# SoC_pwr_2.net
KiCad netlist of a schematic drawn in Altium Designer
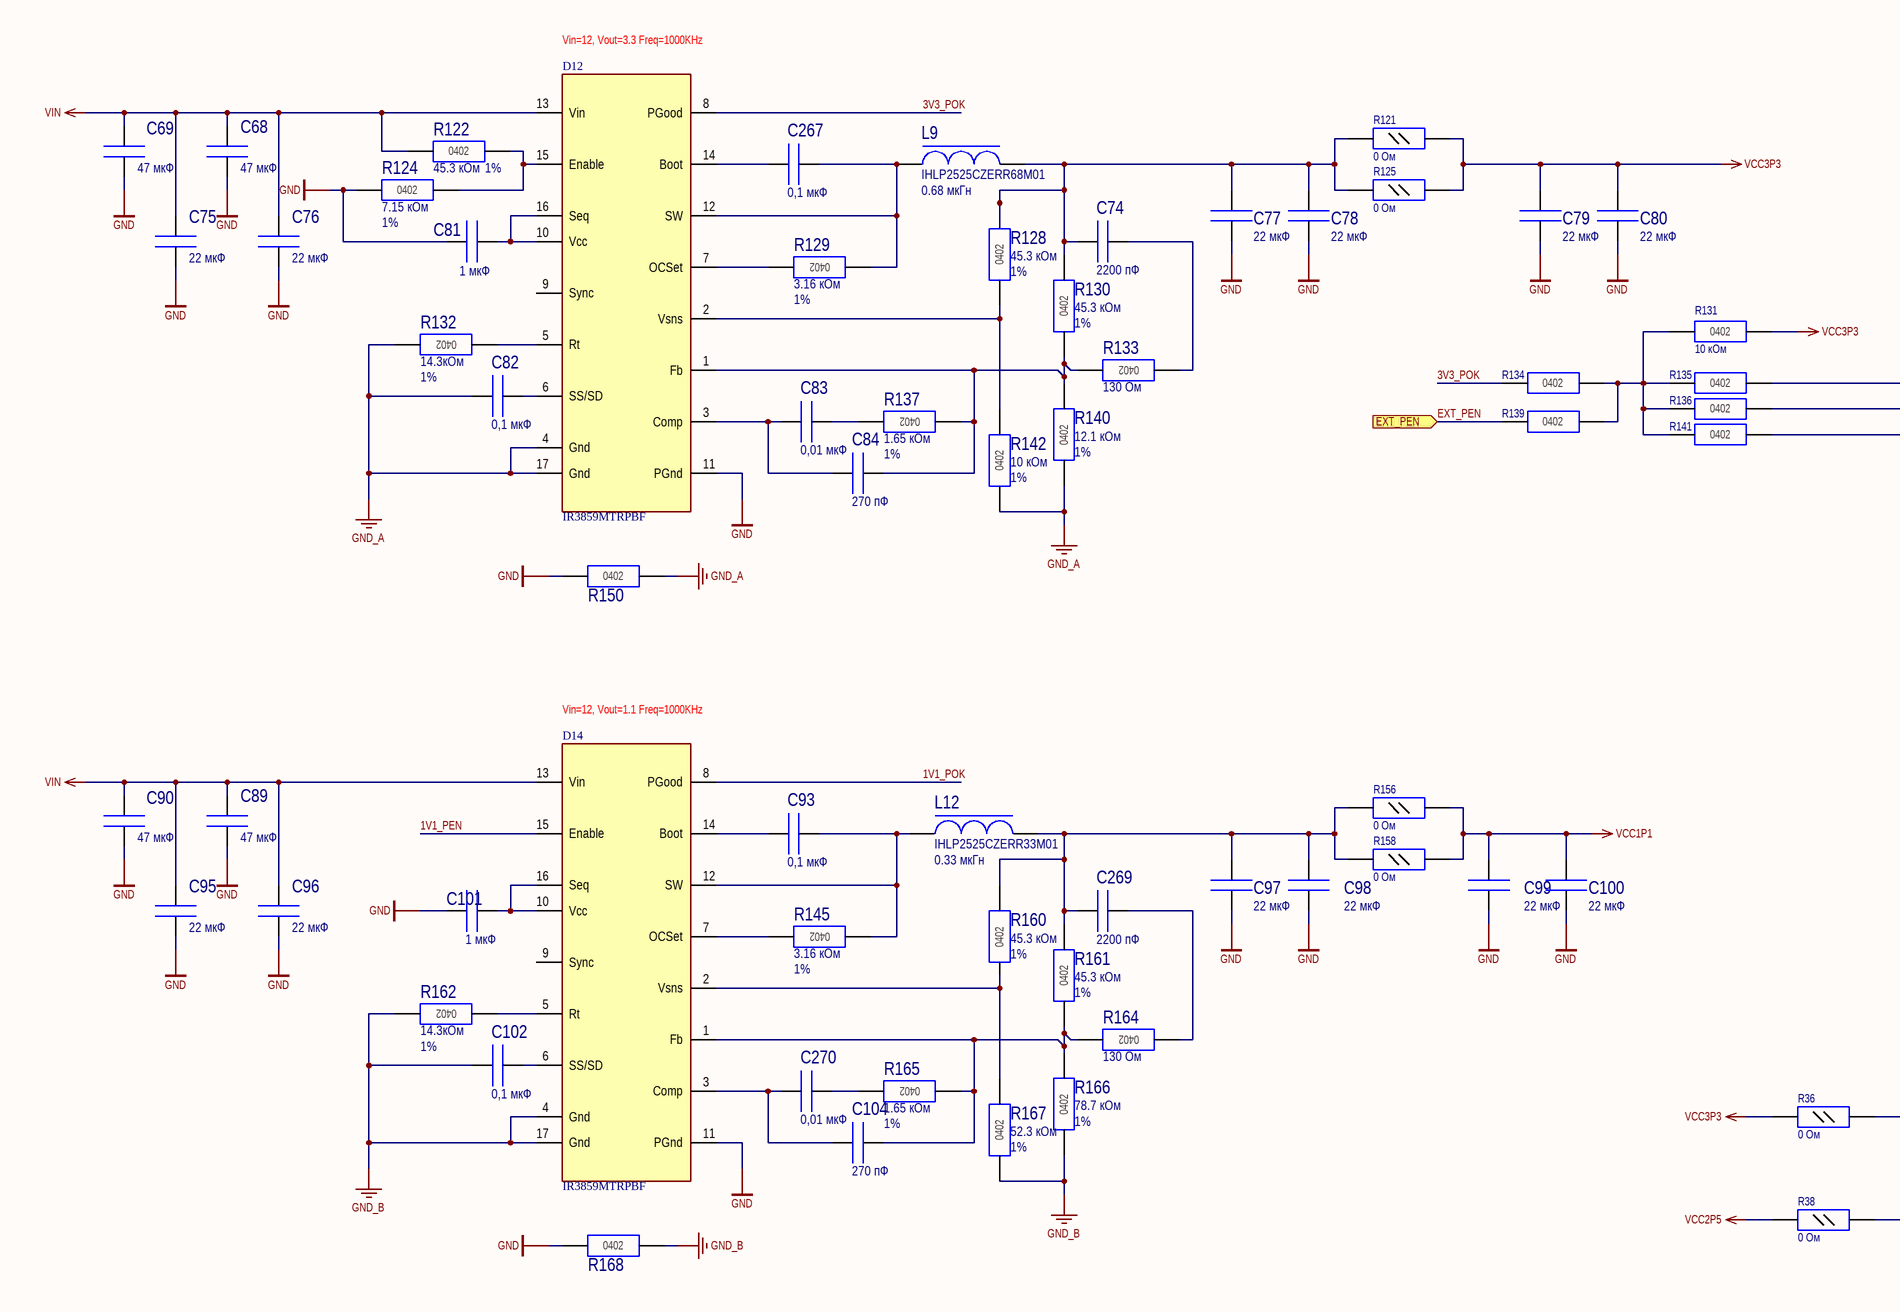
[diagram p0: SoC_pwr_2.SchDoc, left]
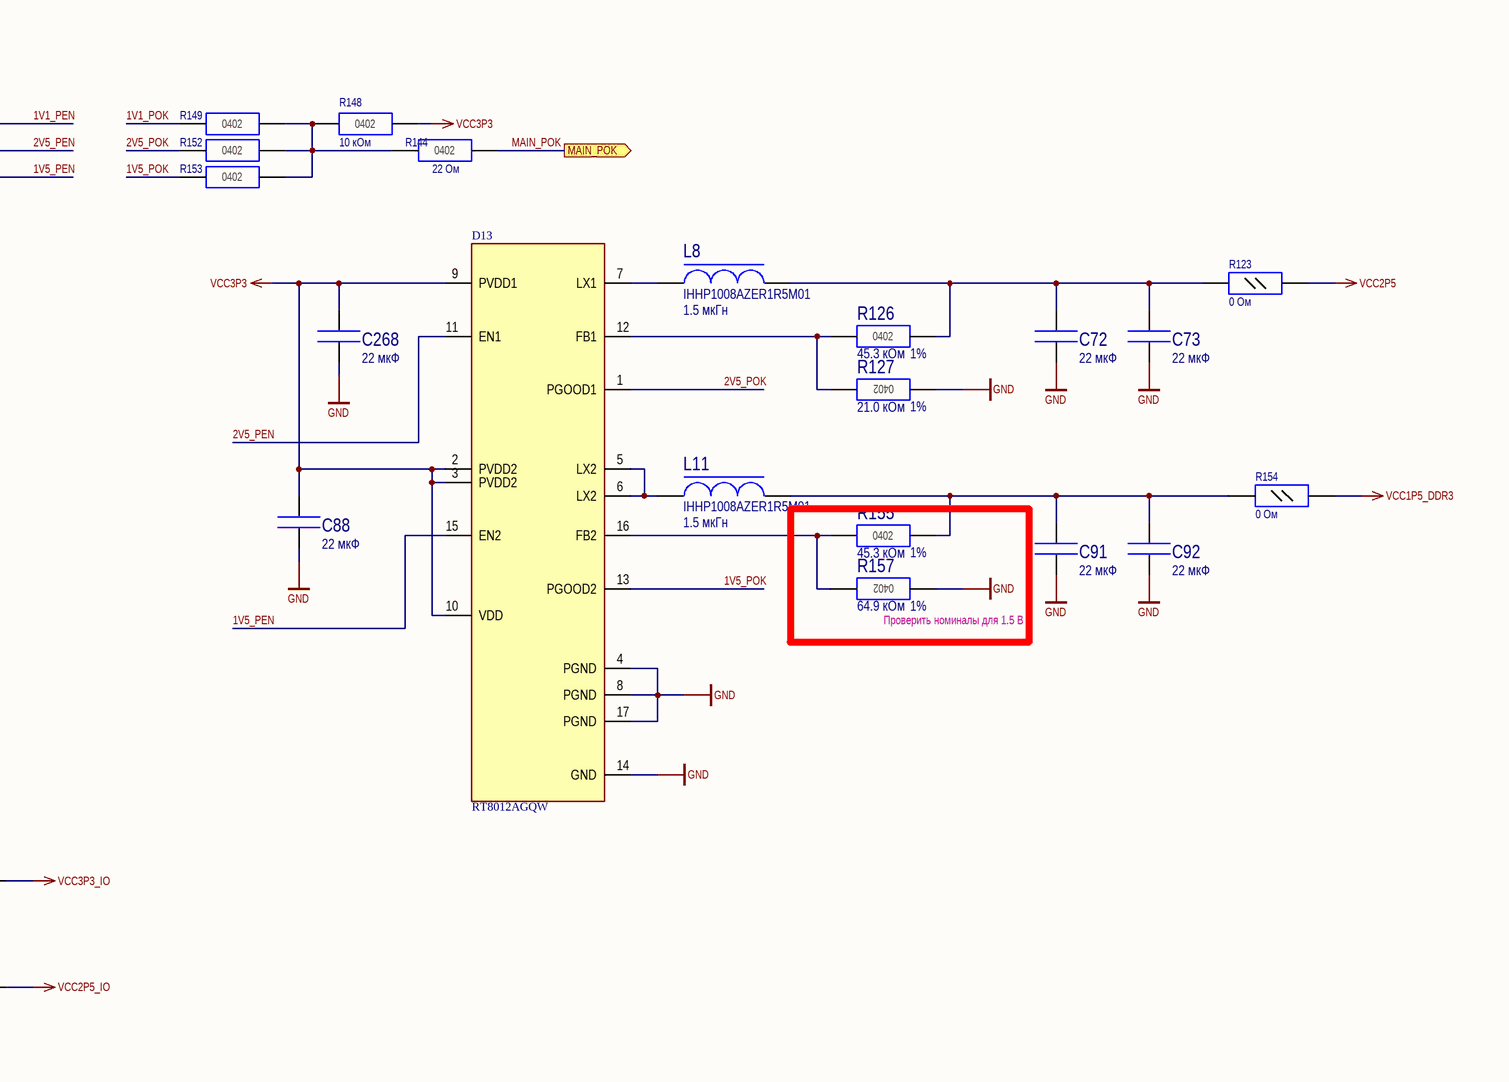
[diagram p1: SoC_pwr_2.SchDoc, right]

(export (version "E")
  (design (tool "Eeschema 10.0.6"))
  (components
    (comp (ref "C68")
      (value "47 мкФ")
      (footprint "CC0603")
      (description "Чип конденсатор керамический")
      (fields (field (name "Comment") "CC0603-X5R-47 мкФ-20%-6,3В"))
      (libsource (lib "Конденсаторы") (part "CC0603-X5R-#-20%-6,3В"))
    )
    (comp (ref "C69")
      (value "47 мкФ")
      (footprint "CC0603")
      (description "Чип конденсатор керамический")
      (fields (field (name "Comment") "CC0603-X5R-47 мкФ-20%-6,3В"))
      (libsource (lib "Конденсаторы") (part "CC0603-X5R-#-20%-6,3В"))
    )
    (comp (ref "C72")
      (value "22 мкФ")
      (footprint "CC0603")
      (description "Чип конденсатор керамический")
      (fields (field (name "Comment") "CC0603-X5R-22 мкФ-20%-6,3В"))
      (libsource (lib "Конденсаторы") (part "CC0603-X5R-#-20%-6,3В"))
    )
    (comp (ref "C73")
      (value "22 мкФ")
      (footprint "CC0603")
      (description "Чип конденсатор керамический")
      (fields (field (name "Comment") "CC0603-X5R-22 мкФ-20%-6,3В"))
      (libsource (lib "Конденсаторы") (part "CC0603-X5R-#-20%-6,3В"))
    )
    (comp (ref "C74")
      (value "2200 пФ")
      (footprint "CC0402(1005)")
      (description "Чип конденсатор керамический")
      (fields (field (name "Comment") "CC0402-X7R-2200 пФ-10%-16В"))
      (libsource (lib "Чип конденсаторы") (part "CC0402-X7R-#-20%-10В"))
    )
    (comp (ref "C75")
      (value "22 мкФ")
      (footprint "CC0603")
      (description "Чип конденсатор керамический")
      (fields (field (name "Comment") "CC0603-X5R-22 мкФ-20%-6,3В"))
      (libsource (lib "Конденсаторы") (part "CC0603-X5R-#-20%-6,3В"))
    )
    (comp (ref "C76")
      (value "22 мкФ")
      (footprint "CC0603")
      (description "Чип конденсатор керамический")
      (fields (field (name "Comment") "CC0603-X5R-22 мкФ-20%-6,3В"))
      (libsource (lib "Конденсаторы") (part "CC0603-X5R-#-20%-6,3В"))
    )
    (comp (ref "C77")
      (value "22 мкФ")
      (footprint "CC0603")
      (description "Чип конденсатор керамический")
      (fields (field (name "Comment") "CC0603-X5R-22 мкФ-20%-6,3В"))
      (libsource (lib "Конденсаторы") (part "CC0603-X5R-#-20%-6,3В"))
    )
    (comp (ref "C78")
      (value "22 мкФ")
      (footprint "CC0603")
      (description "Чип конденсатор керамический")
      (fields (field (name "Comment") "CC0603-X5R-22 мкФ-20%-6,3В"))
      (libsource (lib "Конденсаторы") (part "CC0603-X5R-#-20%-6,3В"))
    )
    (comp (ref "C79")
      (value "22 мкФ")
      (footprint "CC0603")
      (description "Чип конденсатор керамический")
      (fields (field (name "Comment") "CC0603-X5R-22 мкФ-20%-6,3В"))
      (libsource (lib "Конденсаторы") (part "CC0603-X5R-#-20%-6,3В"))
    )
    (comp (ref "C80")
      (value "22 мкФ")
      (footprint "CC0603")
      (description "Чип конденсатор керамический")
      (fields (field (name "Comment") "CC0603-X5R-22 мкФ-20%-6,3В"))
      (libsource (lib "Конденсаторы") (part "CC0603-X5R-#-20%-6,3В"))
    )
    (comp (ref "C81")
      (value "1 мкФ")
      (footprint "CC0603")
      (description "Чип конденсатор керамический")
      (fields (field (name "Comment") "CC0603-X5R-1 мкФ-10%-25В"))
      (libsource (lib "Конденсаторы") (part "CC0603-X5R-#-20%-6,3В"))
    )
    (comp (ref "C82")
      (value "0,1 мкФ")
      (footprint "CC0402(1005)")
      (description "Чип конденсатор керамический")
      (fields (field (name "Comment") "CC0402-X7R-0,1 мкФ-20%-10В"))
      (libsource (lib "Чип конденсаторы") (part "CC0402-X7R-#-20%-10В"))
    )
    (comp (ref "C83")
      (value "0,01 мкФ")
      (footprint "CC0402(1005)")
      (description "Чип конденсатор керамический")
      (fields (field (name "Comment") "CC0402-X7R-0,01 мкФ-10%-50В"))
      (libsource (lib "Чип конденсаторы") (part "CC0402-X7R-#-20%-10В"))
    )
    (comp (ref "C84")
      (value "270 пФ")
      (footprint "CC0402(1005)")
      (description "Чип конденсатор керамический")
      (fields (field (name "Comment") "CC0402-NP0-270 пФ-1%-50В"))
      (libsource (lib "Чип конденсаторы") (part "CC0402-X7R-#-20%-10В"))
    )
    (comp (ref "C88")
      (value "22 мкФ")
      (footprint "CC0603")
      (description "Чип конденсатор керамический")
      (fields (field (name "Comment") "CC0603-X5R-22 мкФ-20%-6,3В"))
      (libsource (lib "Конденсаторы") (part "CC0603-X5R-#-20%-6,3В"))
    )
    (comp (ref "C89")
      (value "47 мкФ")
      (footprint "CC0603")
      (description "Чип конденсатор керамический")
      (fields (field (name "Comment") "CC0603-X5R-47 мкФ-20%-6,3В"))
      (libsource (lib "Конденсаторы") (part "CC0603-X5R-#-20%-6,3В"))
    )
    (comp (ref "C90")
      (value "47 мкФ")
      (footprint "CC0603")
      (description "Чип конденсатор керамический")
      (fields (field (name "Comment") "CC0603-X5R-47 мкФ-20%-6,3В"))
      (libsource (lib "Конденсаторы") (part "CC0603-X5R-#-20%-6,3В"))
    )
    (comp (ref "C91")
      (value "22 мкФ")
      (footprint "CC0603")
      (description "Чип конденсатор керамический")
      (fields (field (name "Comment") "CC0603-X5R-22 мкФ-20%-6,3В"))
      (libsource (lib "Конденсаторы") (part "CC0603-X5R-#-20%-6,3В"))
    )
    (comp (ref "C92")
      (value "22 мкФ")
      (footprint "CC0603")
      (description "Чип конденсатор керамический")
      (fields (field (name "Comment") "CC0603-X5R-22 мкФ-20%-6,3В"))
      (libsource (lib "Конденсаторы") (part "CC0603-X5R-#-20%-6,3В"))
    )
    (comp (ref "C93")
      (value "0,1 мкФ")
      (footprint "CC0402(1005)")
      (description "Чип конденсатор керамический")
      (fields (field (name "Comment") "CC0402-X7R-0,1 мкФ-20%-10В"))
      (libsource (lib "Чип конденсаторы") (part "CC0402-X7R-#-20%-10В"))
    )
    (comp (ref "C95")
      (value "22 мкФ")
      (footprint "CC0603")
      (description "Чип конденсатор керамический")
      (fields (field (name "Comment") "CC0603-X5R-22 мкФ-20%-6,3В"))
      (libsource (lib "Конденсаторы") (part "CC0603-X5R-#-20%-6,3В"))
    )
    (comp (ref "C96")
      (value "22 мкФ")
      (footprint "CC0603")
      (description "Чип конденсатор керамический")
      (fields (field (name "Comment") "CC0603-X5R-22 мкФ-20%-6,3В"))
      (libsource (lib "Конденсаторы") (part "CC0603-X5R-#-20%-6,3В"))
    )
    (comp (ref "C97")
      (value "22 мкФ")
      (footprint "CC0603")
      (description "Чип конденсатор керамический")
      (fields (field (name "Comment") "CC0603-X5R-22 мкФ-20%-6,3В"))
      (libsource (lib "Конденсаторы") (part "CC0603-X5R-#-20%-6,3В"))
    )
    (comp (ref "C98")
      (value "22 мкФ")
      (footprint "CC0603")
      (description "Чип конденсатор керамический")
      (fields (field (name "Comment") "CC0603-X5R-22 мкФ-20%-6,3В"))
      (libsource (lib "Конденсаторы") (part "CC0603-X5R-#-20%-6,3В"))
    )
    (comp (ref "C99")
      (value "22 мкФ")
      (footprint "CC0603")
      (description "Чип конденсатор керамический")
      (fields (field (name "Comment") "CC0603-X5R-22 мкФ-20%-6,3В"))
      (libsource (lib "Конденсаторы") (part "CC0603-X5R-#-20%-6,3В"))
    )
    (comp (ref "C100")
      (value "22 мкФ")
      (footprint "CC0603")
      (description "Чип конденсатор керамический")
      (fields (field (name "Comment") "CC0603-X5R-22 мкФ-20%-6,3В"))
      (libsource (lib "Конденсаторы") (part "CC0603-X5R-#-20%-6,3В"))
    )
    (comp (ref "C101")
      (value "1 мкФ")
      (footprint "CC0603")
      (description "Чип конденсатор керамический")
      (fields (field (name "Comment") "CC0603-X5R-1 мкФ-10%-25В"))
      (libsource (lib "Конденсаторы") (part "CC0603-X5R-#-20%-6,3В"))
    )
    (comp (ref "C102")
      (value "0,1 мкФ")
      (footprint "CC0402(1005)")
      (description "Чип конденсатор керамический")
      (fields (field (name "Comment") "CC0402-X7R-0,1 мкФ-20%-10В"))
      (libsource (lib "Чип конденсаторы") (part "CC0402-X7R-#-20%-10В"))
    )
    (comp (ref "C104")
      (value "270 пФ")
      (footprint "CC0402(1005)")
      (description "Чип конденсатор керамический")
      (fields (field (name "Comment") "CC0402-NP0-270 пФ-1%-50В"))
      (libsource (lib "Чип конденсаторы") (part "CC0402-X7R-#-20%-10В"))
    )
    (comp (ref "C267")
      (value "0,1 мкФ")
      (footprint "CC0402(1005)")
      (description "Чип конденсатор керамический")
      (fields (field (name "Comment") "CC0402-X7R-0,1 мкФ-20%-10В"))
      (libsource (lib "Чип конденсаторы") (part "CC0402-X7R-#-20%-10В"))
    )
    (comp (ref "C268")
      (value "22 мкФ")
      (footprint "CC0603")
      (description "Чип конденсатор керамический")
      (fields (field (name "Comment") "CC0603-X5R-22 мкФ-20%-6,3В"))
      (libsource (lib "Конденсаторы") (part "CC0603-X5R-#-20%-6,3В"))
    )
    (comp (ref "C269")
      (value "2200 пФ")
      (footprint "CC0402(1005)")
      (description "Чип конденсатор керамический")
      (fields (field (name "Comment") "CC0402-X7R-2200 пФ-10%-16В"))
      (libsource (lib "Чип конденсаторы") (part "CC0402-X7R-#-20%-10В"))
    )
    (comp (ref "C270")
      (value "0,01 мкФ")
      (footprint "CC0402(1005)")
      (description "Чип конденсатор керамический")
      (fields (field (name "Comment") "CC0402-X7R-0,01 мкФ-10%-50В"))
      (libsource (lib "Чип конденсаторы") (part "CC0402-X7R-#-20%-10В"))
    )
    (comp (ref "D12")
      (value "IR3859MTRPBF")
      (footprint "IR3859")
      (description "IC REG BUCK ADJ 9A SYNC 17PQFN")
      (libsource (lib "SD_IC") (part "IR3859MPbF"))
    )
    (comp (ref "D13")
      (value "RT8012AGQW")
      (footprint "RT8012AGQW")
      (libsource (lib "SD_IC") (part "RT8012AGQW"))
    )
    (comp (ref "D14")
      (value "IR3859MTRPBF")
      (footprint "IR3859")
      (description "IC REG BUCK ADJ 9A SYNC 17PQFN")
      (libsource (lib "SD_IC") (part "IR3859MPbF"))
    )
    (comp (ref "L8")
      (value "IHHP1008AZER1R5M01")
      (footprint "INDC2720X12L")
      (description "FIXED IND 1.5UH 2.4A 96 MOHM SMD")
      (fields (field (name "ALTIUM_VALUE") "1.5 мкГн"))
      (libsource (lib "SD_IC") (part "L_VISH_IIHHP1008ABE_1"))
    )
    (comp (ref "L9")
      (value "IHLP2525CZERR68M01")
      (footprint "INDP6965X30L")
      (description "FIXED IND 680NH 15.5A 5.5 MOHM")
      (fields (field (name "ALTIUM_VALUE") "0.68 мкГн"))
      (libsource (lib "SD_IC") (part "L_VISH_IHLP2525CZERR68M01"))
    )
    (comp (ref "L11")
      (value "IHHP1008AZER1R5M01")
      (footprint "INDC2720X12L")
      (description "FIXED IND 1.5UH 2.4A 96 MOHM SMD")
      (fields (field (name "ALTIUM_VALUE") "1.5 мкГн"))
      (libsource (lib "SD_IC") (part "L_VISH_IIHHP1008ABE_1"))
    )
    (comp (ref "L12")
      (value "IHLP2525CZERR33M01")
      (footprint "INDP6965X30L")
      (description "FIXED IND 680NH 15.5A 5.5 MOHM")
      (fields (field (name "ALTIUM_VALUE") "0.33 мкГн"))
      (libsource (lib "SD_IC") (part "L_VISH_IHLP2525CZERR68M01"))
    )
    (comp (ref "R36")
      (value "0 Ом")
      (footprint "CR0805")
      (description "Чип резистор")
      (fields (field (name "Comment") "CR0805-0 Ом-±5%"))
      (libsource (lib "Резисторы") (part "CR0805-#-±5%"))
    )
    (comp (ref "R38")
      (value "0 Ом")
      (footprint "CR0805")
      (description "Чип резистор")
      (fields (field (name "Comment") "CR0805-0 Ом-±5%"))
      (libsource (lib "Резисторы") (part "CR0805-#-±5%"))
    )
    (comp (ref "R121")
      (value "0 Ом")
      (footprint "CR0805")
      (description "Чип резистор")
      (fields (field (name "Comment") "CR0805-0 Ом-±5%"))
      (libsource (lib "Резисторы") (part "CR0805-#-±5%"))
    )
    (comp (ref "R122")
      (value "45.3 кОм")
      (footprint "CR0402(1005)")
      (description "Чип резистор")
      (fields (field (name "TOLERANCE") "1%") (field (name "Comment") "CR0402-45.3 кОм-±1%"))
      (libsource (lib "") (part "CR0402-#-±1%_1"))
    )
    (comp (ref "R123")
      (value "0 Ом")
      (footprint "CR0805")
      (description "Чип резистор")
      (fields (field (name "Comment") "CR0805-0 Ом-±5%"))
      (libsource (lib "Резисторы") (part "CR0805-#-±5%"))
    )
    (comp (ref "R124")
      (value "7.15 кОм")
      (footprint "CR0402(1005)")
      (description "Чип резистор")
      (fields (field (name "TOLERANCE") "1%") (field (name "Comment") "CR0402-7.15 кОм-±1%"))
      (libsource (lib "") (part "CR0402-#-±1%_1"))
    )
    (comp (ref "R125")
      (value "0 Ом")
      (footprint "CR0805")
      (description "Чип резистор")
      (fields (field (name "Comment") "CR0805-0 Ом-±5%"))
      (libsource (lib "Резисторы") (part "CR0805-#-±5%"))
    )
    (comp (ref "R126")
      (value "45.3 кОм")
      (footprint "CR0402(1005)")
      (description "Чип резистор")
      (fields (field (name "TOLERANCE") "1%") (field (name "Comment") "CR0402-45.3 кОм-±1%"))
      (libsource (lib "") (part "CR0402-#-±1%_1"))
    )
    (comp (ref "R127")
      (value "21.0 кОм")
      (footprint "CR0402(1005)")
      (description "Чип резистор")
      (fields (field (name "TOLERANCE") "1%") (field (name "Comment") "CR0402-21.0 кОм-±1%"))
      (libsource (lib "") (part "CR0402-#-±1%_2"))
    )
    (comp (ref "R128")
      (value "45.3 кОм")
      (footprint "CR0402(1005)")
      (description "Чип резистор")
      (fields (field (name "TOLERANCE") "1%") (field (name "Comment") "CR0402-45.3 кОм-±1%"))
      (libsource (lib "Чип резисторы") (part "CR0402-#-±1%"))
    )
    (comp (ref "R129")
      (value "3.16 кОм")
      (footprint "CR0402(1005)")
      (description "Чип резистор")
      (fields (field (name "TOLERANCE") "1%") (field (name "Comment") "CR0402-3.16 кОм-±1%"))
      (libsource (lib "") (part "CR0402-#-±1%_2"))
    )
    (comp (ref "R130")
      (value "45.3 кОм")
      (footprint "CR0402(1005)")
      (description "Чип резистор")
      (fields (field (name "TOLERANCE") "1%") (field (name "Comment") "CR0402-45.3 кОм-±1%"))
      (libsource (lib "Чип резисторы") (part "CR0402-#-±1%"))
    )
    (comp (ref "R131")
      (value "10 кОм")
      (footprint "CR0402(1005)")
      (description "Чип резистор")
      (fields (field (name "TOLERANCE") "5%") (field (name "Comment") "CR0402-10 кОм-±5%"))
      (libsource (lib "Резисторы") (part "CR0402-#-±5%"))
    )
    (comp (ref "R132")
      (value "14.3кОм")
      (footprint "CR0402(1005)")
      (description "Чип резистор")
      (fields (field (name "TOLERANCE") "1%") (field (name "Comment") "CR0402-14.3кОм-±1%"))
      (libsource (lib "") (part "CR0402-#-±1%_2"))
    )
    (comp (ref "R133")
      (value "130 Ом")
      (footprint "CR0402(1005)")
      (description "Чип резистор")
      (fields (field (name "Comment") "CR0402-130 Ом-±1%"))
      (libsource (lib "") (part "CR0402-#-±1%_2"))
    )
    (comp (ref "R134")
      (value "CR0402-0 Ом-±5%")
      (footprint "CR0402(1005)")
      (description "Чип резистор")
      (fields (field (name "TOLERANCE") "5%"))
      (libsource (lib "Резисторы") (part "CR0402-#-±5%"))
    )
    (comp (ref "R135")
      (value "CR0402-0 Ом-±5%")
      (footprint "CR0402(1005)")
      (description "Чип резистор")
      (fields (field (name "TOLERANCE") "5%"))
      (libsource (lib "Резисторы") (part "CR0402-#-±5%"))
    )
    (comp (ref "R136")
      (value "CR0402-0 Ом-±5%")
      (footprint "CR0402(1005)")
      (description "Чип резистор")
      (fields (field (name "TOLERANCE") "5%"))
      (libsource (lib "Резисторы") (part "CR0402-#-±5%"))
    )
    (comp (ref "R137")
      (value "1.65 кОм")
      (footprint "CR0402(1005)")
      (description "Чип резистор")
      (fields (field (name "TOLERANCE") "1%") (field (name "Comment") "CR0402-1.65 кОм-±1%"))
      (libsource (lib "") (part "CR0402-#-±1%_2"))
    )
    (comp (ref "R139")
      (value "CR0402-0 Ом-±5%")
      (footprint "CR0402(1005)")
      (description "Чип резистор")
      (fields (field (name "TOLERANCE") "5%"))
      (libsource (lib "Резисторы") (part "CR0402-#-±5%"))
    )
    (comp (ref "R140")
      (value "12.1 кОм")
      (footprint "CR0402(1005)")
      (description "Чип резистор")
      (fields (field (name "TOLERANCE") "1%") (field (name "Comment") "CR0402-12.1 кОм-±1%"))
      (libsource (lib "Чип резисторы") (part "CR0402-#-±1%"))
    )
    (comp (ref "R141")
      (value "CR0402-0 Ом-±5%")
      (footprint "CR0402(1005)")
      (description "Чип резистор")
      (fields (field (name "TOLERANCE") "5%"))
      (libsource (lib "Резисторы") (part "CR0402-#-±5%"))
    )
    (comp (ref "R142")
      (value "10 кОм")
      (footprint "CR0402(1005)")
      (description "Чип резистор")
      (fields (field (name "TOLERANCE") "1%") (field (name "Comment") "CR0402-10 кОм-±1%"))
      (libsource (lib "Чип резисторы") (part "CR0402-#-±1%"))
    )
    (comp (ref "R144")
      (value "22 Ом")
      (footprint "CR0402(1005)")
      (description "Чип резистор")
      (fields (field (name "TOLERANCE") "5%") (field (name "Comment") "CR0402-22 Ом-±5%"))
      (libsource (lib "Чип резисторы") (part "CR0402-#-±5%"))
    )
    (comp (ref "R145")
      (value "3.16 кОм")
      (footprint "CR0402(1005)")
      (description "Чип резистор")
      (fields (field (name "TOLERANCE") "1%") (field (name "Comment") "CR0402-3.16 кОм-±1%"))
      (libsource (lib "") (part "CR0402-#-±1%_2"))
    )
    (comp (ref "R148")
      (value "10 кОм")
      (footprint "CR0402(1005)")
      (description "Чип резистор")
      (fields (field (name "TOLERANCE") "5%") (field (name "Comment") "CR0402-10 кОм-±5%"))
      (libsource (lib "Резисторы") (part "CR0402-#-±5%"))
    )
    (comp (ref "R149")
      (value "CR0402-0 Ом-±5%")
      (footprint "CR0402(1005)")
      (description "Чип резистор")
      (fields (field (name "TOLERANCE") "5%"))
      (libsource (lib "Резисторы") (part "CR0402-#-±5%"))
    )
    (comp (ref "R150")
      (value "CR0402-0 Ом-±5%")
      (footprint "CR0402(1005)")
      (description "Чип резистор")
      (fields (field (name "TOLERANCE") "5%"))
      (libsource (lib "Резисторы") (part "CR0402-#-±5%"))
    )
    (comp (ref "R152")
      (value "CR0402-0 Ом-±5%")
      (footprint "CR0402(1005)")
      (description "Чип резистор")
      (fields (field (name "TOLERANCE") "5%"))
      (libsource (lib "Резисторы") (part "CR0402-#-±5%"))
    )
    (comp (ref "R153")
      (value "CR0402-0 Ом-±5%")
      (footprint "CR0402(1005)")
      (description "Чип резистор")
      (fields (field (name "TOLERANCE") "5%"))
      (libsource (lib "Резисторы") (part "CR0402-#-±5%"))
    )
    (comp (ref "R154")
      (value "0 Ом")
      (footprint "CR0805")
      (description "Чип резистор")
      (fields (field (name "Comment") "CR0805-0 Ом-±5%"))
      (libsource (lib "Резисторы") (part "CR0805-#-±5%"))
    )
    (comp (ref "R155")
      (value "45.3 кОм")
      (footprint "CR0402(1005)")
      (description "Чип резистор")
      (fields (field (name "TOLERANCE") "1%") (field (name "Comment") "CR0402-45.3 кОм-±1%"))
      (libsource (lib "") (part "CR0402-#-±1%_1"))
    )
    (comp (ref "R156")
      (value "0 Ом")
      (footprint "CR0805")
      (description "Чип резистор")
      (fields (field (name "Comment") "CR0805-0 Ом-±5%"))
      (libsource (lib "Резисторы") (part "CR0805-#-±5%"))
    )
    (comp (ref "R157")
      (value "64.9 кОм")
      (footprint "CR0402(1005)")
      (description "Чип резистор")
      (fields (field (name "TOLERANCE") "1%") (field (name "Comment") "CR0402-64.9 кОм-±1%"))
      (libsource (lib "") (part "CR0402-#-±1%_2"))
    )
    (comp (ref "R158")
      (value "0 Ом")
      (footprint "CR0805")
      (description "Чип резистор")
      (fields (field (name "Comment") "CR0805-0 Ом-±5%"))
      (libsource (lib "Резисторы") (part "CR0805-#-±5%"))
    )
    (comp (ref "R160")
      (value "45.3 кОм")
      (footprint "CR0402(1005)")
      (description "Чип резистор")
      (fields (field (name "TOLERANCE") "1%") (field (name "Comment") "CR0402-45.3 кОм-±1%"))
      (libsource (lib "Чип резисторы") (part "CR0402-#-±1%"))
    )
    (comp (ref "R161")
      (value "45.3 кОм")
      (footprint "CR0402(1005)")
      (description "Чип резистор")
      (fields (field (name "TOLERANCE") "1%") (field (name "Comment") "CR0402-45.3 кОм-±1%"))
      (libsource (lib "Чип резисторы") (part "CR0402-#-±1%"))
    )
    (comp (ref "R162")
      (value "14.3кОм")
      (footprint "CR0402(1005)")
      (description "Чип резистор")
      (fields (field (name "TOLERANCE") "1%") (field (name "Comment") "CR0402-14.3кОм-±1%"))
      (libsource (lib "") (part "CR0402-#-±1%_2"))
    )
    (comp (ref "R164")
      (value "130 Ом")
      (footprint "CR0402(1005)")
      (description "Чип резистор")
      (fields (field (name "Comment") "CR0402-130 Ом-±1%"))
      (libsource (lib "") (part "CR0402-#-±1%_2"))
    )
    (comp (ref "R165")
      (value "1.65 кОм")
      (footprint "CR0402(1005)")
      (description "Чип резистор")
      (fields (field (name "TOLERANCE") "1%") (field (name "Comment") "CR0402-1.65 кОм-±1%"))
      (libsource (lib "") (part "CR0402-#-±1%_2"))
    )
    (comp (ref "R166")
      (value "78.7 кОм")
      (footprint "CR0402(1005)")
      (description "Чип резистор")
      (fields (field (name "TOLERANCE") "1%") (field (name "Comment") "CR0402-78.7 кОм-±1%"))
      (libsource (lib "Чип резисторы") (part "CR0402-#-±1%"))
    )
    (comp (ref "R167")
      (value "52.3 кОм")
      (footprint "CR0402(1005)")
      (description "Чип резистор")
      (fields (field (name "TOLERANCE") "1%") (field (name "Comment") "CR0402-52.3 кОм-±1%"))
      (libsource (lib "Чип резисторы") (part "CR0402-#-±1%"))
    )
    (comp (ref "R168")
      (value "CR0402-0 Ом-±5%")
      (footprint "CR0402(1005)")
      (description "Чип резистор")
      (fields (field (name "TOLERANCE") "5%"))
      (libsource (lib "Резисторы") (part "CR0402-#-±5%"))
    )
  )
  (nets
    (net (code "1") (name "/1V1_PEN") (class "Default")
      (node (ref "D14") (pin "15") (pinfunction "Enable_15") (pintype "passive"))
      (node (ref "R135") (pin "2") (pinfunction "-_2") (pintype "passive"))
    )
    (net (code "2") (name "/1V1_POK") (class "Default")
      (node (ref "D14") (pin "8") (pinfunction "PGood_8") (pintype "passive"))
      (node (ref "R149") (pin "1") (pinfunction "+_1") (pintype "passive"))
    )
    (net (code "3") (name "/1V5_PEN") (class "Default")
      (node (ref "D13") (pin "15") (pinfunction "EN2_15") (pintype "passive"))
      (node (ref "R141") (pin "2") (pinfunction "-_2") (pintype "passive"))
    )
    (net (code "4") (name "/1V5_POK") (class "Default")
      (node (ref "D13") (pin "13") (pinfunction "PGOOD2_13") (pintype "passive"))
      (node (ref "R153") (pin "1") (pinfunction "+_1") (pintype "passive"))
    )
    (net (code "5") (name "/2V5_PEN") (class "Default")
      (node (ref "D13") (pin "11") (pinfunction "EN1_11") (pintype "passive"))
      (node (ref "R136") (pin "2") (pinfunction "-_2") (pintype "passive"))
    )
    (net (code "6") (name "/2V5_POK") (class "Default")
      (node (ref "D13") (pin "1") (pinfunction "PGOOD1_1") (pintype "passive"))
      (node (ref "R152") (pin "1") (pinfunction "+_1") (pintype "passive"))
    )
    (net (code "7") (name "/3V3_POK") (class "Default")
      (node (ref "D12") (pin "8") (pinfunction "PGood_8") (pintype "passive"))
      (node (ref "R134") (pin "1") (pinfunction "+_1") (pintype "passive"))
    )
    (net (code "8") (name "/EXT_PEN") (class "Default")
      (node (ref "R139") (pin "1") (pinfunction "+_1") (pintype "passive"))
    )
    (net (code "9") (name "/MAIN_POK") (class "Default")
      (node (ref "R144") (pin "2") (pinfunction "-_2") (pintype "passive"))
    )
    (net (code "10") (name "GND") (class "Default")
      (node (ref "C100") (pin "2") (pinfunction "-_2") (pintype "passive"))
      (node (ref "C101") (pin "1") (pinfunction "+_1") (pintype "passive"))
      (node (ref "C268") (pin "2") (pinfunction "-_2") (pintype "passive"))
      (node (ref "C68") (pin "2") (pinfunction "-_2") (pintype "passive"))
      (node (ref "C69") (pin "2") (pinfunction "-_2") (pintype "passive"))
      (node (ref "C72") (pin "2") (pinfunction "-_2") (pintype "passive"))
      (node (ref "C73") (pin "2") (pinfunction "-_2") (pintype "passive"))
      (node (ref "C75") (pin "2") (pinfunction "-_2") (pintype "passive"))
      (node (ref "C76") (pin "2") (pinfunction "-_2") (pintype "passive"))
      (node (ref "C77") (pin "2") (pinfunction "-_2") (pintype "passive"))
      (node (ref "C78") (pin "2") (pinfunction "-_2") (pintype "passive"))
      (node (ref "C79") (pin "2") (pinfunction "-_2") (pintype "passive"))
      (node (ref "C80") (pin "2") (pinfunction "-_2") (pintype "passive"))
      (node (ref "C81") (pin "1") (pinfunction "+_1") (pintype "passive"))
      (node (ref "C88") (pin "2") (pinfunction "-_2") (pintype "passive"))
      (node (ref "C89") (pin "2") (pinfunction "-_2") (pintype "passive"))
      (node (ref "C90") (pin "2") (pinfunction "-_2") (pintype "passive"))
      (node (ref "C91") (pin "2") (pinfunction "-_2") (pintype "passive"))
      (node (ref "C92") (pin "2") (pinfunction "-_2") (pintype "passive"))
      (node (ref "C95") (pin "2") (pinfunction "-_2") (pintype "passive"))
      (node (ref "C96") (pin "2") (pinfunction "-_2") (pintype "passive"))
      (node (ref "C97") (pin "2") (pinfunction "-_2") (pintype "passive"))
      (node (ref "C98") (pin "2") (pinfunction "-_2") (pintype "passive"))
      (node (ref "C99") (pin "2") (pinfunction "-_2") (pintype "passive"))
      (node (ref "D12") (pin "11") (pinfunction "PGnd_11") (pintype "passive"))
      (node (ref "D13") (pin "14") (pinfunction "GND_14") (pintype "passive"))
      (node (ref "D13") (pin "17") (pinfunction "PGND_17") (pintype "passive"))
      (node (ref "D13") (pin "4") (pinfunction "PGND_4") (pintype "passive"))
      (node (ref "D13") (pin "8") (pinfunction "PGND_8") (pintype "passive"))
      (node (ref "D14") (pin "11") (pinfunction "PGnd_11") (pintype "passive"))
      (node (ref "R124") (pin "1") (pinfunction "+_1") (pintype "passive"))
      (node (ref "R127") (pin "1") (pinfunction "+_1") (pintype "passive"))
      (node (ref "R150") (pin "1") (pinfunction "+_1") (pintype "passive"))
      (node (ref "R157") (pin "1") (pinfunction "+_1") (pintype "passive"))
      (node (ref "R168") (pin "1") (pinfunction "+_1") (pintype "passive"))
    )
    (net (code "11") (name "GND_A") (class "Default")
      (node (ref "C82") (pin "1") (pinfunction "+_1") (pintype "passive"))
      (node (ref "D12") (pin "17") (pinfunction "Gnd_17") (pintype "passive"))
      (node (ref "D12") (pin "4") (pinfunction "Gnd_4") (pintype "passive"))
      (node (ref "R132") (pin "2") (pinfunction "-_2") (pintype "passive"))
      (node (ref "R140") (pin "1") (pinfunction "+_1") (pintype "passive"))
      (node (ref "R142") (pin "1") (pinfunction "+_1") (pintype "passive"))
      (node (ref "R150") (pin "2") (pinfunction "-_2") (pintype "passive"))
    )
    (net (code "12") (name "GND_B") (class "Default")
      (node (ref "C102") (pin "1") (pinfunction "+_1") (pintype "passive"))
      (node (ref "D14") (pin "17") (pinfunction "Gnd_17") (pintype "passive"))
      (node (ref "D14") (pin "4") (pinfunction "Gnd_4") (pintype "passive"))
      (node (ref "R162") (pin "2") (pinfunction "-_2") (pintype "passive"))
      (node (ref "R166") (pin "1") (pinfunction "+_1") (pintype "passive"))
      (node (ref "R167") (pin "1") (pinfunction "+_1") (pintype "passive"))
      (node (ref "R168") (pin "2") (pinfunction "-_2") (pintype "passive"))
    )
    (net (code "13") (name "Net-(C72-+)") (class "Default")
      (node (ref "C72") (pin "1") (pinfunction "+_1") (pintype "passive"))
      (node (ref "C73") (pin "1") (pinfunction "+_1") (pintype "passive"))
      (node (ref "L8") (pin "2") (pinfunction "2_2") (pintype "passive"))
      (node (ref "R123") (pin "1") (pinfunction "+_1") (pintype "passive"))
      (node (ref "R126") (pin "2") (pinfunction "-_2") (pintype "passive"))
    )
    (net (code "14") (name "Net-(C74-+)") (class "Default")
      (node (ref "C74") (pin "1") (pinfunction "+_1") (pintype "passive"))
      (node (ref "R133") (pin "1") (pinfunction "+_1") (pintype "passive"))
    )
    (net (code "15") (name "Net-(C74--)") (class "Default")
      (node (ref "C74") (pin "2") (pinfunction "-_2") (pintype "passive"))
      (node (ref "C77") (pin "1") (pinfunction "+_1") (pintype "passive"))
      (node (ref "C78") (pin "1") (pinfunction "+_1") (pintype "passive"))
      (node (ref "L9") (pin "2") (pinfunction "2_2") (pintype "passive"))
      (node (ref "R121") (pin "1") (pinfunction "+_1") (pintype "passive"))
      (node (ref "R125") (pin "1") (pinfunction "+_1") (pintype "passive"))
      (node (ref "R128") (pin "2") (pinfunction "-_2") (pintype "passive"))
      (node (ref "R130") (pin "2") (pinfunction "-_2") (pintype "passive"))
    )
    (net (code "16") (name "Net-(C81--)") (class "Default")
      (node (ref "C81") (pin "2") (pinfunction "-_2") (pintype "passive"))
      (node (ref "D12") (pin "10") (pinfunction "Vcc_10") (pintype "passive"))
      (node (ref "D12") (pin "16") (pinfunction "Seq_16") (pintype "passive"))
    )
    (net (code "17") (name "Net-(C82--)") (class "Default")
      (node (ref "C82") (pin "2") (pinfunction "-_2") (pintype "passive"))
      (node (ref "D12") (pin "6") (pinfunction "SS/SD_6") (pintype "passive"))
    )
    (net (code "18") (name "Net-(C83-+)") (class "Default")
      (node (ref "C83") (pin "1") (pinfunction "+_1") (pintype "passive"))
      (node (ref "C84") (pin "2") (pinfunction "-_2") (pintype "passive"))
      (node (ref "D12") (pin "3") (pinfunction "Comp_3") (pintype "passive"))
    )
    (net (code "19") (name "Net-(C83--)") (class "Default")
      (node (ref "C83") (pin "2") (pinfunction "-_2") (pintype "passive"))
      (node (ref "R137") (pin "2") (pinfunction "-_2") (pintype "passive"))
    )
    (net (code "20") (name "Net-(C84-+)") (class "Default")
      (node (ref "C84") (pin "1") (pinfunction "+_1") (pintype "passive"))
      (node (ref "D12") (pin "1") (pinfunction "Fb_1") (pintype "passive"))
      (node (ref "R130") (pin "1") (pinfunction "+_1") (pintype "passive"))
      (node (ref "R133") (pin "2") (pinfunction "-_2") (pintype "passive"))
      (node (ref "R137") (pin "1") (pinfunction "+_1") (pintype "passive"))
      (node (ref "R140") (pin "2") (pinfunction "-_2") (pintype "passive"))
    )
    (net (code "21") (name "Net-(C91-+)") (class "Default")
      (node (ref "C91") (pin "1") (pinfunction "+_1") (pintype "passive"))
      (node (ref "C92") (pin "1") (pinfunction "+_1") (pintype "passive"))
      (node (ref "L11") (pin "2") (pinfunction "2_2") (pintype "passive"))
      (node (ref "R154") (pin "1") (pinfunction "+_1") (pintype "passive"))
      (node (ref "R155") (pin "2") (pinfunction "-_2") (pintype "passive"))
    )
    (net (code "22") (name "Net-(C93-+)") (class "Default")
      (node (ref "C93") (pin "1") (pinfunction "+_1") (pintype "passive"))
      (node (ref "D14") (pin "14") (pinfunction "Boot_14") (pintype "passive"))
    )
    (net (code "23") (name "Net-(C93--)") (class "Default")
      (node (ref "C93") (pin "2") (pinfunction "-_2") (pintype "passive"))
      (node (ref "D14") (pin "12") (pinfunction "SW_12") (pintype "passive"))
      (node (ref "L12") (pin "1") (pinfunction "1_1") (pintype "passive"))
      (node (ref "R145") (pin "1") (pinfunction "+_1") (pintype "passive"))
    )
    (net (code "24") (name "Net-(C101--)") (class "Default")
      (node (ref "C101") (pin "2") (pinfunction "-_2") (pintype "passive"))
      (node (ref "D14") (pin "10") (pinfunction "Vcc_10") (pintype "passive"))
      (node (ref "D14") (pin "16") (pinfunction "Seq_16") (pintype "passive"))
    )
    (net (code "25") (name "Net-(C102--)") (class "Default")
      (node (ref "C102") (pin "2") (pinfunction "-_2") (pintype "passive"))
      (node (ref "D14") (pin "6") (pinfunction "SS/SD_6") (pintype "passive"))
    )
    (net (code "26") (name "Net-(C104-+)") (class "Default")
      (node (ref "C104") (pin "1") (pinfunction "+_1") (pintype "passive"))
      (node (ref "D14") (pin "1") (pinfunction "Fb_1") (pintype "passive"))
      (node (ref "R161") (pin "1") (pinfunction "+_1") (pintype "passive"))
      (node (ref "R164") (pin "2") (pinfunction "-_2") (pintype "passive"))
      (node (ref "R165") (pin "1") (pinfunction "+_1") (pintype "passive"))
      (node (ref "R166") (pin "2") (pinfunction "-_2") (pintype "passive"))
    )
    (net (code "27") (name "Net-(C104--)") (class "Default")
      (node (ref "C104") (pin "2") (pinfunction "-_2") (pintype "passive"))
      (node (ref "C270") (pin "1") (pinfunction "+_1") (pintype "passive"))
      (node (ref "D14") (pin "3") (pinfunction "Comp_3") (pintype "passive"))
    )
    (net (code "28") (name "Net-(C267-+)") (class "Default")
      (node (ref "C267") (pin "1") (pinfunction "+_1") (pintype "passive"))
      (node (ref "D12") (pin "14") (pinfunction "Boot_14") (pintype "passive"))
    )
    (net (code "29") (name "Net-(C267--)") (class "Default")
      (node (ref "C267") (pin "2") (pinfunction "-_2") (pintype "passive"))
      (node (ref "D12") (pin "12") (pinfunction "SW_12") (pintype "passive"))
      (node (ref "L9") (pin "1") (pinfunction "1_1") (pintype "passive"))
      (node (ref "R129") (pin "1") (pinfunction "+_1") (pintype "passive"))
    )
    (net (code "30") (name "Net-(C269-+)") (class "Default")
      (node (ref "C269") (pin "1") (pinfunction "+_1") (pintype "passive"))
      (node (ref "R164") (pin "1") (pinfunction "+_1") (pintype "passive"))
    )
    (net (code "31") (name "Net-(C269--)") (class "Default")
      (node (ref "C269") (pin "2") (pinfunction "-_2") (pintype "passive"))
      (node (ref "C97") (pin "1") (pinfunction "+_1") (pintype "passive"))
      (node (ref "C98") (pin "1") (pinfunction "+_1") (pintype "passive"))
      (node (ref "L12") (pin "2") (pinfunction "2_2") (pintype "passive"))
      (node (ref "R156") (pin "1") (pinfunction "+_1") (pintype "passive"))
      (node (ref "R158") (pin "1") (pinfunction "+_1") (pintype "passive"))
      (node (ref "R160") (pin "2") (pinfunction "-_2") (pintype "passive"))
      (node (ref "R161") (pin "2") (pinfunction "-_2") (pintype "passive"))
    )
    (net (code "32") (name "Net-(C270--)") (class "Default")
      (node (ref "C270") (pin "2") (pinfunction "-_2") (pintype "passive"))
      (node (ref "R165") (pin "2") (pinfunction "-_2") (pintype "passive"))
    )
    (net (code "33") (name "Net-(D12-Enable)") (class "Default")
      (node (ref "D12") (pin "15") (pinfunction "Enable_15") (pintype "passive"))
      (node (ref "R122") (pin "2") (pinfunction "-_2") (pintype "passive"))
      (node (ref "R124") (pin "2") (pinfunction "-_2") (pintype "passive"))
    )
    (net (code "34") (name "Net-(D12-OCSet)") (class "Default")
      (node (ref "D12") (pin "7") (pinfunction "OCSet_7") (pintype "passive"))
      (node (ref "R129") (pin "2") (pinfunction "-_2") (pintype "passive"))
    )
    (net (code "35") (name "Net-(D12-Rt)") (class "Default")
      (node (ref "D12") (pin "5") (pinfunction "Rt_5") (pintype "passive"))
      (node (ref "R132") (pin "1") (pinfunction "+_1") (pintype "passive"))
    )
    (net (code "36") (name "Net-(D12-Vsns)") (class "Default")
      (node (ref "D12") (pin "2") (pinfunction "Vsns_2") (pintype "passive"))
      (node (ref "R128") (pin "1") (pinfunction "+_1") (pintype "passive"))
      (node (ref "R142") (pin "2") (pinfunction "-_2") (pintype "passive"))
    )
    (net (code "37") (name "Net-(D13-FB1)") (class "Default")
      (node (ref "D13") (pin "12") (pinfunction "FB1_12") (pintype "passive"))
      (node (ref "R126") (pin "1") (pinfunction "+_1") (pintype "passive"))
      (node (ref "R127") (pin "2") (pinfunction "-_2") (pintype "passive"))
    )
    (net (code "38") (name "Net-(D13-FB2)") (class "Default")
      (node (ref "D13") (pin "16") (pinfunction "FB2_16") (pintype "passive"))
      (node (ref "R155") (pin "1") (pinfunction "+_1") (pintype "passive"))
      (node (ref "R157") (pin "2") (pinfunction "-_2") (pintype "passive"))
    )
    (net (code "39") (name "Net-(D13-LX1)") (class "Default")
      (node (ref "D13") (pin "7") (pinfunction "LX1_7") (pintype "passive"))
      (node (ref "L8") (pin "1") (pinfunction "1_1") (pintype "passive"))
    )
    (net (code "40") (name "Net-(D13-LX2-Pad5)") (class "Default")
      (node (ref "D13") (pin "5") (pinfunction "LX2_5") (pintype "passive"))
      (node (ref "D13") (pin "6") (pinfunction "LX2_6") (pintype "passive"))
      (node (ref "L11") (pin "1") (pinfunction "1_1") (pintype "passive"))
    )
    (net (code "41") (name "Net-(D14-OCSet)") (class "Default")
      (node (ref "D14") (pin "7") (pinfunction "OCSet_7") (pintype "passive"))
      (node (ref "R145") (pin "2") (pinfunction "-_2") (pintype "passive"))
    )
    (net (code "42") (name "Net-(D14-Rt)") (class "Default")
      (node (ref "D14") (pin "5") (pinfunction "Rt_5") (pintype "passive"))
      (node (ref "R162") (pin "1") (pinfunction "+_1") (pintype "passive"))
    )
    (net (code "43") (name "Net-(D14-Vsns)") (class "Default")
      (node (ref "D14") (pin "2") (pinfunction "Vsns_2") (pintype "passive"))
      (node (ref "R160") (pin "1") (pinfunction "+_1") (pintype "passive"))
      (node (ref "R167") (pin "2") (pinfunction "-_2") (pintype "passive"))
    )
    (net (code "44") (name "Net-(R131-+)") (class "Default")
      (node (ref "R131") (pin "1") (pinfunction "+_1") (pintype "passive"))
      (node (ref "R134") (pin "2") (pinfunction "-_2") (pintype "passive"))
      (node (ref "R135") (pin "1") (pinfunction "+_1") (pintype "passive"))
      (node (ref "R136") (pin "1") (pinfunction "+_1") (pintype "passive"))
      (node (ref "R139") (pin "2") (pinfunction "-_2") (pintype "passive"))
      (node (ref "R141") (pin "1") (pinfunction "+_1") (pintype "passive"))
    )
    (net (code "45") (name "Net-(R144-+)") (class "Default")
      (node (ref "R144") (pin "1") (pinfunction "+_1") (pintype "passive"))
      (node (ref "R148") (pin "1") (pinfunction "+_1") (pintype "passive"))
      (node (ref "R149") (pin "2") (pinfunction "-_2") (pintype "passive"))
      (node (ref "R152") (pin "2") (pinfunction "-_2") (pintype "passive"))
      (node (ref "R153") (pin "2") (pinfunction "-_2") (pintype "passive"))
    )
    (net (code "46") (name "VCC1P1") (class "Default")
      (node (ref "C100") (pin "1") (pinfunction "+_1") (pintype "passive"))
      (node (ref "C99") (pin "1") (pinfunction "+_1") (pintype "passive"))
      (node (ref "R156") (pin "2") (pinfunction "-_2") (pintype "passive"))
      (node (ref "R158") (pin "2") (pinfunction "-_2") (pintype "passive"))
    )
    (net (code "47") (name "VCC1P5_DDR3") (class "Default")
      (node (ref "R154") (pin "2") (pinfunction "-_2") (pintype "passive"))
    )
    (net (code "48") (name "VCC2P5") (class "Default")
      (node (ref "R123") (pin "2") (pinfunction "-_2") (pintype "passive"))
      (node (ref "R38") (pin "1") (pinfunction "+_1") (pintype "passive"))
    )
    (net (code "49") (name "VCC2P5_IO") (class "Default")
      (node (ref "R38") (pin "2") (pinfunction "-_2") (pintype "passive"))
    )
    (net (code "50") (name "VCC3P3") (class "Default")
      (node (ref "C268") (pin "1") (pinfunction "+_1") (pintype "passive"))
      (node (ref "C79") (pin "1") (pinfunction "+_1") (pintype "passive"))
      (node (ref "C80") (pin "1") (pinfunction "+_1") (pintype "passive"))
      (node (ref "C88") (pin "1") (pinfunction "+_1") (pintype "passive"))
      (node (ref "D13") (pin "10") (pinfunction "VDD_10") (pintype "passive"))
      (node (ref "D13") (pin "2") (pinfunction "PVDD2_2") (pintype "passive"))
      (node (ref "D13") (pin "3") (pinfunction "PVDD2_3") (pintype "passive"))
      (node (ref "D13") (pin "9") (pinfunction "PVDD1_9") (pintype "passive"))
      (node (ref "R121") (pin "2") (pinfunction "-_2") (pintype "passive"))
      (node (ref "R125") (pin "2") (pinfunction "-_2") (pintype "passive"))
      (node (ref "R131") (pin "2") (pinfunction "-_2") (pintype "passive"))
      (node (ref "R148") (pin "2") (pinfunction "-_2") (pintype "passive"))
      (node (ref "R36") (pin "1") (pinfunction "+_1") (pintype "passive"))
    )
    (net (code "51") (name "VCC3P3_IO") (class "Default")
      (node (ref "R36") (pin "2") (pinfunction "-_2") (pintype "passive"))
    )
    (net (code "52") (name "VIN") (class "Default")
      (node (ref "C68") (pin "1") (pinfunction "+_1") (pintype "passive"))
      (node (ref "C69") (pin "1") (pinfunction "+_1") (pintype "passive"))
      (node (ref "C75") (pin "1") (pinfunction "+_1") (pintype "passive"))
      (node (ref "C76") (pin "1") (pinfunction "+_1") (pintype "passive"))
      (node (ref "C89") (pin "1") (pinfunction "+_1") (pintype "passive"))
      (node (ref "C90") (pin "1") (pinfunction "+_1") (pintype "passive"))
      (node (ref "C95") (pin "1") (pinfunction "+_1") (pintype "passive"))
      (node (ref "C96") (pin "1") (pinfunction "+_1") (pintype "passive"))
      (node (ref "D12") (pin "13") (pinfunction "Vin_13") (pintype "passive"))
      (node (ref "D14") (pin "13") (pinfunction "Vin_13") (pintype "passive"))
      (node (ref "R122") (pin "1") (pinfunction "+_1") (pintype "passive"))
    )
    (net (code "53") (name "unconnected-(D12-Sync-Pad9)") (class "Default")
      (node (ref "D12") (pin "9") (pinfunction "Sync_9") (pintype "passive"))
    )
    (net (code "54") (name "unconnected-(D14-Sync-Pad9)") (class "Default")
      (node (ref "D14") (pin "9") (pinfunction "Sync_9") (pintype "passive"))
    )
  )
)
